# daclock-3_1.net
KiCad netlist of a schematic drawn in EAGLE
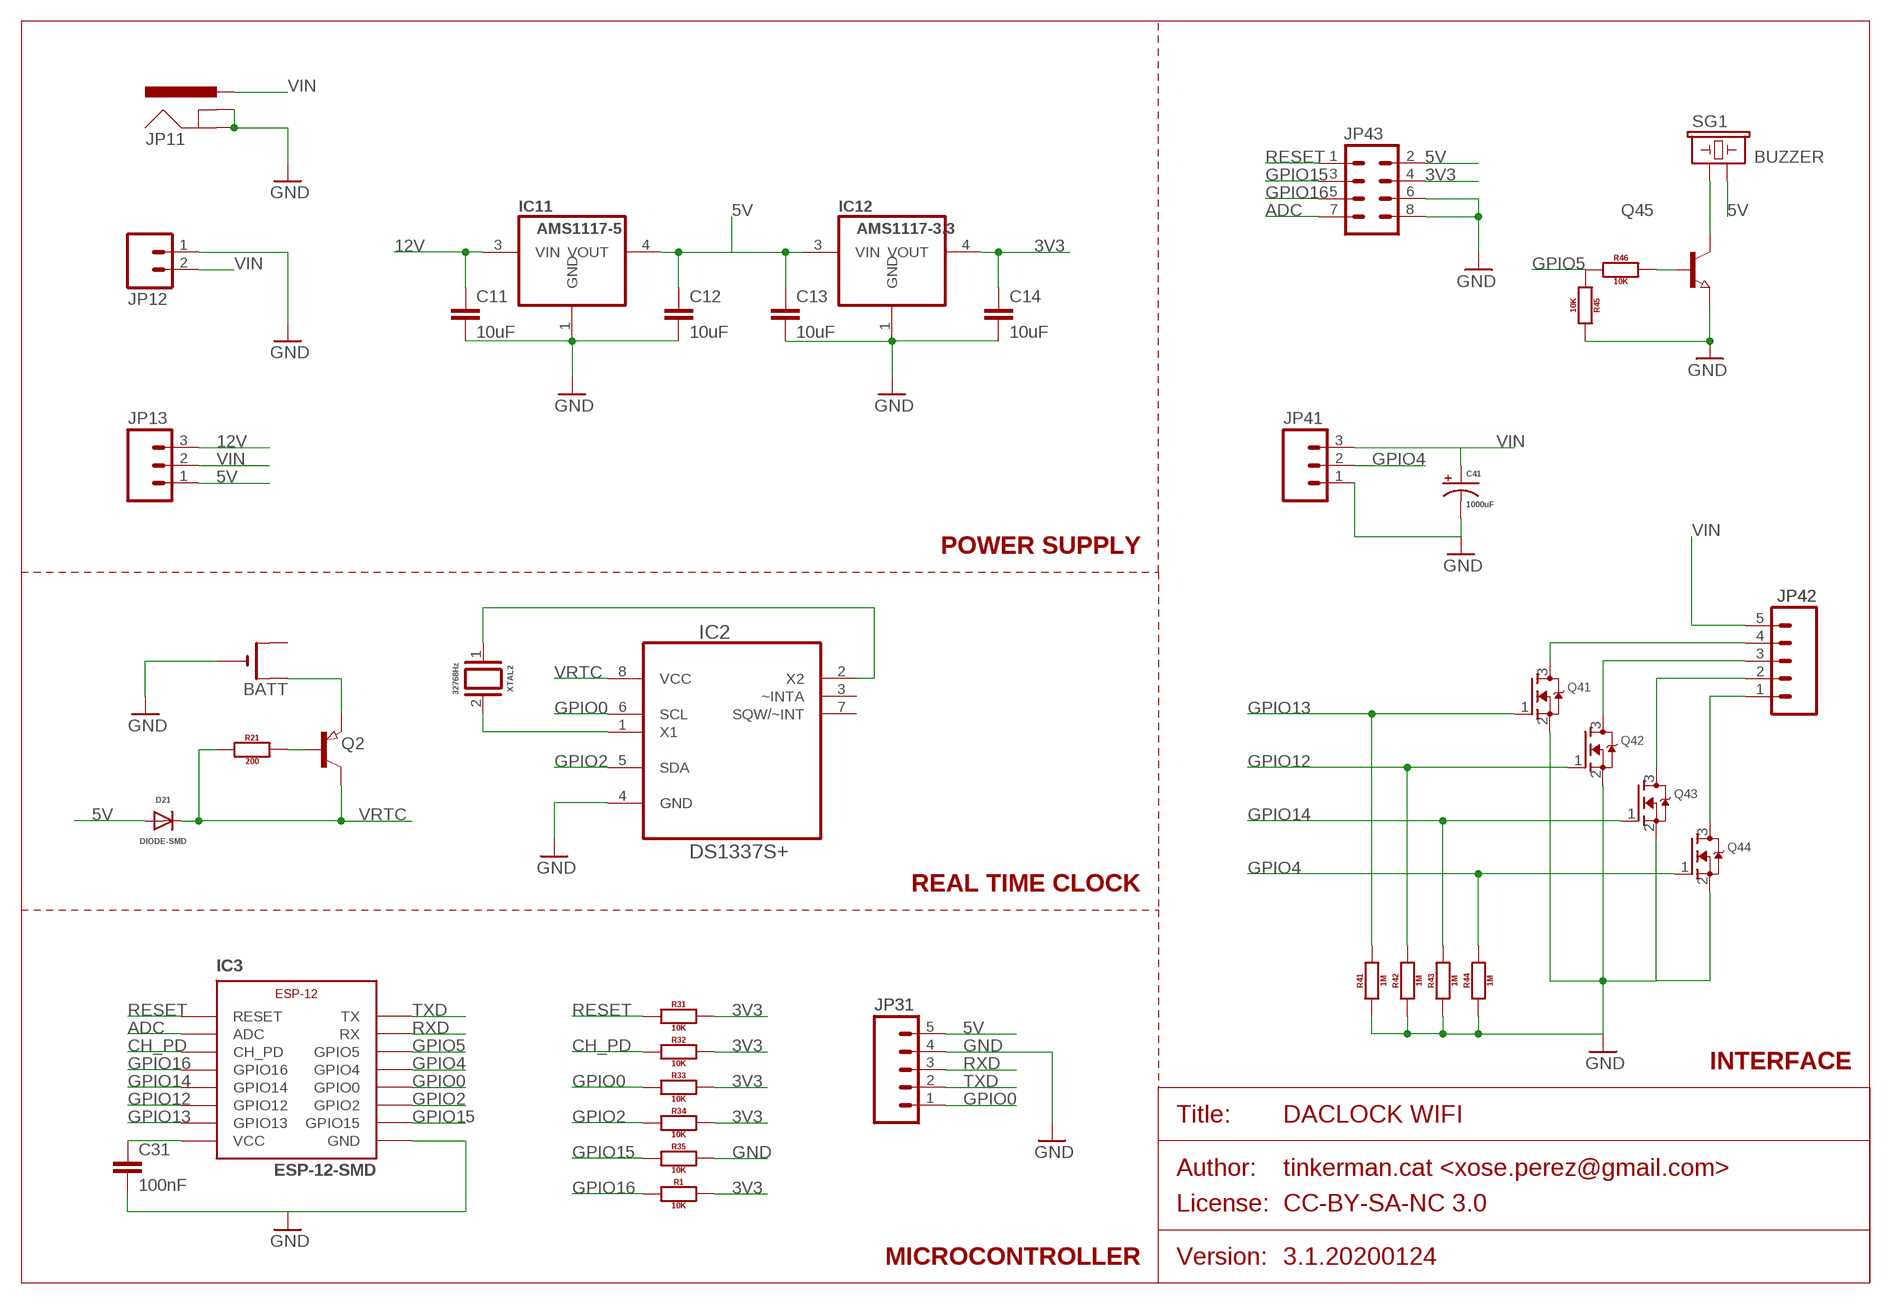
[diagram p0: schematic, sheet 1]

(export (version "E")
  (design (tool "Eeschema 10.0.6"))
  (components
    (comp (ref "BATT")
      (value "CR2032SMT")
      (footprint "eagle-import:CR2032-SMD")
      (libsource (lib "eagle-import") (part "CR2032SMT"))
    )
    (comp (ref "C11")
      (value "10uF")
      (footprint "eagle-import:0805")
      (libsource (lib "eagle-import") (part "C-EU0805"))
    )
    (comp (ref "C12")
      (value "10uF")
      (footprint "eagle-import:0805")
      (libsource (lib "eagle-import") (part "C-EU0805"))
    )
    (comp (ref "C13")
      (value "10uF")
      (footprint "eagle-import:0805")
      (libsource (lib "eagle-import") (part "C-EU0805"))
    )
    (comp (ref "C14")
      (value "10uF")
      (footprint "eagle-import:0805")
      (libsource (lib "eagle-import") (part "C-EU0805"))
    )
    (comp (ref "C31")
      (value "100nF")
      (footprint "eagle-import:0805")
      (libsource (lib "eagle-import") (part "C-EU0805"))
    )
    (comp (ref "C41")
      (value "1000uF")
      (footprint "eagle-import:PANASONIC_G")
      (libsource (lib "eagle-import") (part "CAP_POLG"))
    )
    (comp (ref "D21")
      (value "DIODE-SMD")
      (footprint "eagle-import:0805_DIODE")
      (libsource (lib "eagle-import") (part "DIODE-SMD"))
    )
    (comp (ref "IC2")
      (value "DS1337S+")
      (footprint "eagle-import:SOIC127P600X175-8N")
      (libsource (lib "eagle-import") (part "DS1337S+"))
    )
    (comp (ref "IC3")
      (value "ESP-12-SMD")
      (footprint "eagle-import:ESP-12-SMD")
      (libsource (lib "eagle-import") (part "ESP-12-SMD"))
    )
    (comp (ref "IC11")
      (value "AMS1117-5")
      (footprint "eagle-import:SOT223")
      (libsource (lib "eagle-import") (part "REG1117SOT223-2"))
    )
    (comp (ref "IC12")
      (value "AMS1117-3.3")
      (footprint "eagle-import:SOT223")
      (libsource (lib "eagle-import") (part "REG1117SOT223-2"))
    )
    (comp (ref "JP11")
      (value "POWER_JACKPTH")
      (footprint "eagle-import:POWER_JACK_PTH")
      (libsource (lib "eagle-import") (part "POWER_JACKPTH"))
    )
    (comp (ref "JP12")
      (value "M02200MIL")
      (footprint "eagle-import:SCREWTERMINAL-200MIL-2")
      (libsource (lib "eagle-import") (part "M02200MIL"))
    )
    (comp (ref "JP13")
      (value "M03PTH")
      (footprint "eagle-import:1X03")
      (libsource (lib "eagle-import") (part "M03PTH"))
    )
    (comp (ref "JP31")
      (value "M05NO_SILK")
      (footprint "eagle-import:1X05_NO_SILK")
      (libsource (lib "eagle-import") (part "M05NO_SILK"))
    )
    (comp (ref "JP41")
      (value "M03200MIL")
      (footprint "eagle-import:SCREWTERMINAL-200MIL-3")
      (libsource (lib "eagle-import") (part "M03200MIL"))
    )
    (comp (ref "JP42")
      (value "M05NO_SILK")
      (footprint "eagle-import:1X05_NO_SILK")
      (libsource (lib "eagle-import") (part "M05NO_SILK"))
    )
    (comp (ref "JP43")
      (value "M04X2")
      (footprint "eagle-import:2X4")
      (libsource (lib "eagle-import") (part "M04X2"))
    )
    (comp (ref "Q2")
      (value "PNP-TRANSISTOR_SOT23")
      (footprint "eagle-import:SOT23")
      (libsource (lib "eagle-import") (part "PNP-TRANSISTOR_SOT23"))
    )
    (comp (ref "Q41")
      (value "MOSFET-NREFLOW")
      (footprint "eagle-import:SOT23")
      (libsource (lib "eagle-import") (part "MOSFET-NREFLOW"))
    )
    (comp (ref "Q42")
      (value "MOSFET-NREFLOW")
      (footprint "eagle-import:SOT23")
      (libsource (lib "eagle-import") (part "MOSFET-NREFLOW"))
    )
    (comp (ref "Q43")
      (value "MOSFET-NREFLOW")
      (footprint "eagle-import:SOT23")
      (libsource (lib "eagle-import") (part "MOSFET-NREFLOW"))
    )
    (comp (ref "Q44")
      (value "MOSFET-NREFLOW")
      (footprint "eagle-import:SOT23")
      (libsource (lib "eagle-import") (part "MOSFET-NREFLOW"))
    )
    (comp (ref "Q45")
      (value "NPN-TRANSISTOR_SOT23")
      (footprint "eagle-import:SOT23")
      (libsource (lib "eagle-import") (part "NPN-TRANSISTOR_SOT23"))
    )
    (comp (ref "R1")
      (value "10K")
      (footprint "eagle-import:0805")
      (libsource (lib "eagle-import") (part "RESISTOR0805"))
    )
    (comp (ref "R21")
      (value "200")
      (footprint "eagle-import:0805")
      (libsource (lib "eagle-import") (part "RESISTOR0805"))
    )
    (comp (ref "R31")
      (value "10K")
      (footprint "eagle-import:0805")
      (libsource (lib "eagle-import") (part "RESISTOR0805"))
    )
    (comp (ref "R32")
      (value "10K")
      (footprint "eagle-import:0805")
      (libsource (lib "eagle-import") (part "RESISTOR0805"))
    )
    (comp (ref "R33")
      (value "10K")
      (footprint "eagle-import:0805")
      (libsource (lib "eagle-import") (part "RESISTOR0805"))
    )
    (comp (ref "R34")
      (value "10K")
      (footprint "eagle-import:0805")
      (libsource (lib "eagle-import") (part "RESISTOR0805"))
    )
    (comp (ref "R35")
      (value "10K")
      (footprint "eagle-import:0805")
      (libsource (lib "eagle-import") (part "RESISTOR0805"))
    )
    (comp (ref "R41")
      (value "1M")
      (footprint "eagle-import:0805")
      (libsource (lib "eagle-import") (part "RESISTOR0805"))
    )
    (comp (ref "R42")
      (value "1M")
      (footprint "eagle-import:0805")
      (libsource (lib "eagle-import") (part "RESISTOR0805"))
    )
    (comp (ref "R43")
      (value "1M")
      (footprint "eagle-import:0805")
      (libsource (lib "eagle-import") (part "RESISTOR0805"))
    )
    (comp (ref "R44")
      (value "1M")
      (footprint "eagle-import:0805")
      (libsource (lib "eagle-import") (part "RESISTOR0805"))
    )
    (comp (ref "R45")
      (value "10K")
      (footprint "eagle-import:0805")
      (libsource (lib "eagle-import") (part "RESISTOR0805"))
    )
    (comp (ref "R46")
      (value "10K")
      (footprint "eagle-import:0805")
      (libsource (lib "eagle-import") (part "RESISTOR0805"))
    )
    (comp (ref "SG1")
      (value "BUZZER")
      (footprint "eagle-import:BUZZER-12MM")
      (libsource (lib "eagle-import") (part "BUZZERPTH"))
    )
    (comp (ref "XTAL2")
      (value "32768Hz")
      (footprint "eagle-import:TC38H")
      (libsource (lib "eagle-import") (part "CRYSTAL_TC38H"))
    )
  )
  (nets
    (net (code "1") (name "/3V3") (class "Default")
      (node (ref "C14") (pin "1") (pinfunction "1_1") (pintype "passive"))
      (node (ref "C31") (pin "1") (pinfunction "1_1") (pintype "passive"))
      (node (ref "IC12") (pin "4") (pinfunction "VOUT_4") (pintype "output"))
      (node (ref "IC3") (pin "VCC") (pinfunction "VCC_VCC") (pintype "bidirectional"))
      (node (ref "JP43") (pin "4") (pinfunction "4_4") (pintype "passive"))
      (node (ref "R1") (pin "2") (pinfunction "2_2") (pintype "passive"))
      (node (ref "R31") (pin "2") (pinfunction "2_2") (pintype "passive"))
      (node (ref "R32") (pin "2") (pinfunction "2_2") (pintype "passive"))
      (node (ref "R33") (pin "2") (pinfunction "2_2") (pintype "passive"))
      (node (ref "R34") (pin "2") (pinfunction "2_2") (pintype "passive"))
    )
    (net (code "2") (name "/5V") (class "Default")
      (node (ref "C12") (pin "1") (pinfunction "1_1") (pintype "passive"))
      (node (ref "C13") (pin "1") (pinfunction "1_1") (pintype "passive"))
      (node (ref "D21") (pin "A") (pinfunction "A_A") (pintype "passive"))
      (node (ref "IC11") (pin "4") (pinfunction "VOUT_4") (pintype "output"))
      (node (ref "IC12") (pin "3") (pinfunction "VIN_3") (pintype "input"))
      (node (ref "JP13") (pin "1") (pinfunction "1_1") (pintype "passive"))
      (node (ref "JP31") (pin "5") (pinfunction "5_5") (pintype "passive"))
      (node (ref "JP43") (pin "2") (pinfunction "2_2") (pintype "passive"))
      (node (ref "SG1") (pin "-") (pinfunction "2_-") (pintype "passive"))
    )
    (net (code "3") (name "/12V") (class "Default")
      (node (ref "C11") (pin "1") (pinfunction "1_1") (pintype "passive"))
      (node (ref "IC11") (pin "3") (pinfunction "VIN_3") (pintype "input"))
      (node (ref "JP13") (pin "3") (pinfunction "3_3") (pintype "passive"))
    )
    (net (code "4") (name "/ADC") (class "Default")
      (node (ref "IC3") (pin "ADC") (pinfunction "ADC_ADC") (pintype "bidirectional"))
      (node (ref "JP43") (pin "7") (pinfunction "7_7") (pintype "passive"))
    )
    (net (code "5") (name "/CH_PD") (class "Default")
      (node (ref "IC3") (pin "CH_PD") (pinfunction "CH_PD_CH_PD") (pintype "bidirectional"))
      (node (ref "R32") (pin "1") (pinfunction "1_1") (pintype "passive"))
    )
    (net (code "6") (name "/GPIO0") (class "Default")
      (node (ref "IC2") (pin "6") (pinfunction "SCL_6") (pintype "input"))
      (node (ref "IC3") (pin "GPIO0") (pinfunction "GPIO0_GPIO0") (pintype "bidirectional"))
      (node (ref "JP31") (pin "1") (pinfunction "1_1") (pintype "passive"))
      (node (ref "R33") (pin "1") (pinfunction "1_1") (pintype "passive"))
    )
    (net (code "7") (name "/GPIO2") (class "Default")
      (node (ref "IC2") (pin "5") (pinfunction "SDA_5") (pintype "bidirectional"))
      (node (ref "IC3") (pin "GPIO2") (pinfunction "GPIO2_GPIO2") (pintype "bidirectional"))
      (node (ref "R34") (pin "1") (pinfunction "1_1") (pintype "passive"))
    )
    (net (code "8") (name "/GPIO4") (class "Default")
      (node (ref "IC3") (pin "GPIO4") (pinfunction "GPIO4_GPIO4") (pintype "bidirectional"))
      (node (ref "JP41") (pin "2") (pinfunction "2_2") (pintype "passive"))
      (node (ref "Q44") (pin "1") (pinfunction "G_1") (pintype "bidirectional"))
      (node (ref "R44") (pin "2") (pinfunction "2_2") (pintype "passive"))
    )
    (net (code "9") (name "/GPIO5") (class "Default")
      (node (ref "IC3") (pin "GPIO5") (pinfunction "GPIO5_GPIO5") (pintype "bidirectional"))
      (node (ref "R45") (pin "1") (pinfunction "1_1") (pintype "passive"))
      (node (ref "R46") (pin "1") (pinfunction "1_1") (pintype "passive"))
    )
    (net (code "10") (name "/GPIO12") (class "Default")
      (node (ref "IC3") (pin "GPIO12") (pinfunction "GPIO12_GPIO12") (pintype "bidirectional"))
      (node (ref "Q42") (pin "1") (pinfunction "G_1") (pintype "bidirectional"))
      (node (ref "R42") (pin "2") (pinfunction "2_2") (pintype "passive"))
    )
    (net (code "11") (name "/GPIO13") (class "Default")
      (node (ref "IC3") (pin "GPIO13") (pinfunction "GPIO13_GPIO13") (pintype "bidirectional"))
      (node (ref "Q41") (pin "1") (pinfunction "G_1") (pintype "bidirectional"))
      (node (ref "R41") (pin "2") (pinfunction "2_2") (pintype "passive"))
    )
    (net (code "12") (name "/GPIO14") (class "Default")
      (node (ref "IC3") (pin "GPIO14") (pinfunction "GPIO14_GPIO14") (pintype "bidirectional"))
      (node (ref "Q43") (pin "1") (pinfunction "G_1") (pintype "bidirectional"))
      (node (ref "R43") (pin "2") (pinfunction "2_2") (pintype "passive"))
    )
    (net (code "13") (name "/GPIO15") (class "Default")
      (node (ref "IC3") (pin "GPIO15") (pinfunction "GPIO15_GPIO15") (pintype "bidirectional"))
      (node (ref "JP43") (pin "3") (pinfunction "3_3") (pintype "passive"))
      (node (ref "R35") (pin "1") (pinfunction "1_1") (pintype "passive"))
    )
    (net (code "14") (name "/GPIO16") (class "Default")
      (node (ref "IC3") (pin "GPIO16") (pinfunction "GPIO16_GPIO16") (pintype "bidirectional"))
      (node (ref "JP43") (pin "5") (pinfunction "5_5") (pintype "passive"))
      (node (ref "R1") (pin "1") (pinfunction "1_1") (pintype "passive"))
    )
    (net (code "15") (name "/RESET") (class "Default")
      (node (ref "IC3") (pin "RESET") (pinfunction "RESET_RESET") (pintype "bidirectional"))
      (node (ref "JP43") (pin "1") (pinfunction "1_1") (pintype "passive"))
      (node (ref "R31") (pin "1") (pinfunction "1_1") (pintype "passive"))
    )
    (net (code "16") (name "/RXD") (class "Default")
      (node (ref "IC3") (pin "RX") (pinfunction "RX_RX") (pintype "bidirectional"))
      (node (ref "JP31") (pin "3") (pinfunction "3_3") (pintype "passive"))
    )
    (net (code "17") (name "/TXD") (class "Default")
      (node (ref "IC3") (pin "TX") (pinfunction "TX_TX") (pintype "bidirectional"))
      (node (ref "JP31") (pin "2") (pinfunction "2_2") (pintype "passive"))
    )
    (net (code "18") (name "/VIN") (class "Default")
      (node (ref "C41") (pin "+") (pinfunction "+_+") (pintype "passive"))
      (node (ref "JP11") (pin "PWR") (pinfunction "PWR_PWR") (pintype "bidirectional"))
      (node (ref "JP12") (pin "2") (pinfunction "2_2") (pintype "passive"))
      (node (ref "JP13") (pin "2") (pinfunction "2_2") (pintype "passive"))
      (node (ref "JP41") (pin "3") (pinfunction "3_3") (pintype "passive"))
      (node (ref "JP42") (pin "5") (pinfunction "5_5") (pintype "passive"))
    )
    (net (code "19") (name "/VRTC") (class "Default")
      (node (ref "D21") (pin "C") (pinfunction "C_C") (pintype "passive"))
      (node (ref "IC2") (pin "8") (pinfunction "VCC_8") (pintype "power_in"))
      (node (ref "Q2") (pin "3") (pinfunction "C_3") (pintype "passive"))
      (node (ref "R21") (pin "1") (pinfunction "1_1") (pintype "passive"))
    )
    (net (code "20") (name "GND") (class "Default")
      (node (ref "BATT") (pin "-") (pinfunction "-_-") (pintype "passive"))
      (node (ref "C11") (pin "2") (pinfunction "2_2") (pintype "passive"))
      (node (ref "C12") (pin "2") (pinfunction "2_2") (pintype "passive"))
      (node (ref "C13") (pin "2") (pinfunction "2_2") (pintype "passive"))
      (node (ref "C14") (pin "2") (pinfunction "2_2") (pintype "passive"))
      (node (ref "C31") (pin "2") (pinfunction "2_2") (pintype "passive"))
      (node (ref "C41") (pin "-") (pinfunction "-_-") (pintype "passive"))
      (node (ref "IC11") (pin "1") (pinfunction "GND_1") (pintype "power_in"))
      (node (ref "IC12") (pin "1") (pinfunction "GND_1") (pintype "power_in"))
      (node (ref "IC2") (pin "4") (pinfunction "GND_4") (pintype "passive"))
      (node (ref "IC3") (pin "GND") (pinfunction "GND_GND") (pintype "bidirectional"))
      (node (ref "JP11") (pin "GND") (pinfunction "GND_GND") (pintype "bidirectional"))
      (node (ref "JP11") (pin "GNDBREAK") (pinfunction "GNDBREAK_GNDBREAK") (pintype "bidirectional"))
      (node (ref "JP12") (pin "1") (pinfunction "1_1") (pintype "passive"))
      (node (ref "JP31") (pin "4") (pinfunction "4_4") (pintype "passive"))
      (node (ref "JP41") (pin "1") (pinfunction "1_1") (pintype "passive"))
      (node (ref "JP43") (pin "6") (pinfunction "6_6") (pintype "passive"))
      (node (ref "JP43") (pin "8") (pinfunction "8_8") (pintype "passive"))
      (node (ref "Q41") (pin "2") (pinfunction "S_2") (pintype "bidirectional"))
      (node (ref "Q42") (pin "2") (pinfunction "S_2") (pintype "bidirectional"))
      (node (ref "Q43") (pin "2") (pinfunction "S_2") (pintype "bidirectional"))
      (node (ref "Q44") (pin "2") (pinfunction "S_2") (pintype "bidirectional"))
      (node (ref "Q45") (pin "2") (pinfunction "E_2") (pintype "passive"))
      (node (ref "R35") (pin "2") (pinfunction "2_2") (pintype "passive"))
      (node (ref "R41") (pin "1") (pinfunction "1_1") (pintype "passive"))
      (node (ref "R42") (pin "1") (pinfunction "1_1") (pintype "passive"))
      (node (ref "R43") (pin "1") (pinfunction "1_1") (pintype "passive"))
      (node (ref "R44") (pin "1") (pinfunction "1_1") (pintype "passive"))
      (node (ref "R45") (pin "2") (pinfunction "2_2") (pintype "passive"))
    )
    (net (code "21") (name "Net-(BATT-+)") (class "Default")
      (node (ref "BATT") (pin "+$1") (pinfunction "+_+$1") (pintype "passive"))
      (node (ref "Q2") (pin "2") (pinfunction "E_2") (pintype "passive"))
    )
    (net (code "22") (name "Net-(IC2-X1)") (class "Default")
      (node (ref "IC2") (pin "1") (pinfunction "X1_1") (pintype "input"))
      (node (ref "XTAL2") (pin "2") (pinfunction "2_2") (pintype "passive"))
    )
    (net (code "23") (name "Net-(IC2-X2)") (class "Default")
      (node (ref "IC2") (pin "2") (pinfunction "X2_2") (pintype "passive"))
      (node (ref "XTAL2") (pin "1") (pinfunction "1_1") (pintype "passive"))
    )
    (net (code "24") (name "Net-(Q2-B)") (class "Default")
      (node (ref "Q2") (pin "1") (pinfunction "B_1") (pintype "passive"))
      (node (ref "R21") (pin "2") (pinfunction "2_2") (pintype "passive"))
    )
    (net (code "25") (name "Net-(Q41-D)") (class "Default")
      (node (ref "JP42") (pin "4") (pinfunction "4_4") (pintype "passive"))
      (node (ref "Q41") (pin "3") (pinfunction "D_3") (pintype "bidirectional"))
    )
    (net (code "26") (name "Net-(Q42-D)") (class "Default")
      (node (ref "JP42") (pin "3") (pinfunction "3_3") (pintype "passive"))
      (node (ref "Q42") (pin "3") (pinfunction "D_3") (pintype "bidirectional"))
    )
    (net (code "27") (name "Net-(Q43-D)") (class "Default")
      (node (ref "JP42") (pin "2") (pinfunction "2_2") (pintype "passive"))
      (node (ref "Q43") (pin "3") (pinfunction "D_3") (pintype "bidirectional"))
    )
    (net (code "28") (name "Net-(Q44-D)") (class "Default")
      (node (ref "JP42") (pin "1") (pinfunction "1_1") (pintype "passive"))
      (node (ref "Q44") (pin "3") (pinfunction "D_3") (pintype "bidirectional"))
    )
    (net (code "29") (name "Net-(Q45-B)") (class "Default")
      (node (ref "Q45") (pin "1") (pinfunction "B_1") (pintype "passive"))
      (node (ref "R46") (pin "2") (pinfunction "2_2") (pintype "passive"))
    )
    (net (code "30") (name "Net-(Q45-C)") (class "Default")
      (node (ref "Q45") (pin "3") (pinfunction "C_3") (pintype "passive"))
      (node (ref "SG1") (pin "+") (pinfunction "1_+") (pintype "passive"))
    )
    (net (code "31") (name "unconnected-(BATT-+1-Pad+$2)") (class "Default")
      (node (ref "BATT") (pin "+$2") (pinfunction "+1_+$2") (pintype "passive"))
    )
    (net (code "32") (name "unconnected-(IC2-SQW{slash}~{INT}-Pad7)") (class "Default")
      (node (ref "IC2") (pin "7") (pinfunction "SQW/~{INT}_7") (pintype "output"))
    )
    (net (code "33") (name "unconnected-(IC2-~{INTA}-Pad3)") (class "Default")
      (node (ref "IC2") (pin "3") (pinfunction "~{INTA}_3") (pintype "output"))
    )
  )
)
